# SCH_CLAP-SWITCH_2025-06-27.net
KiCad netlist of a schematic drawn in EasyEDA
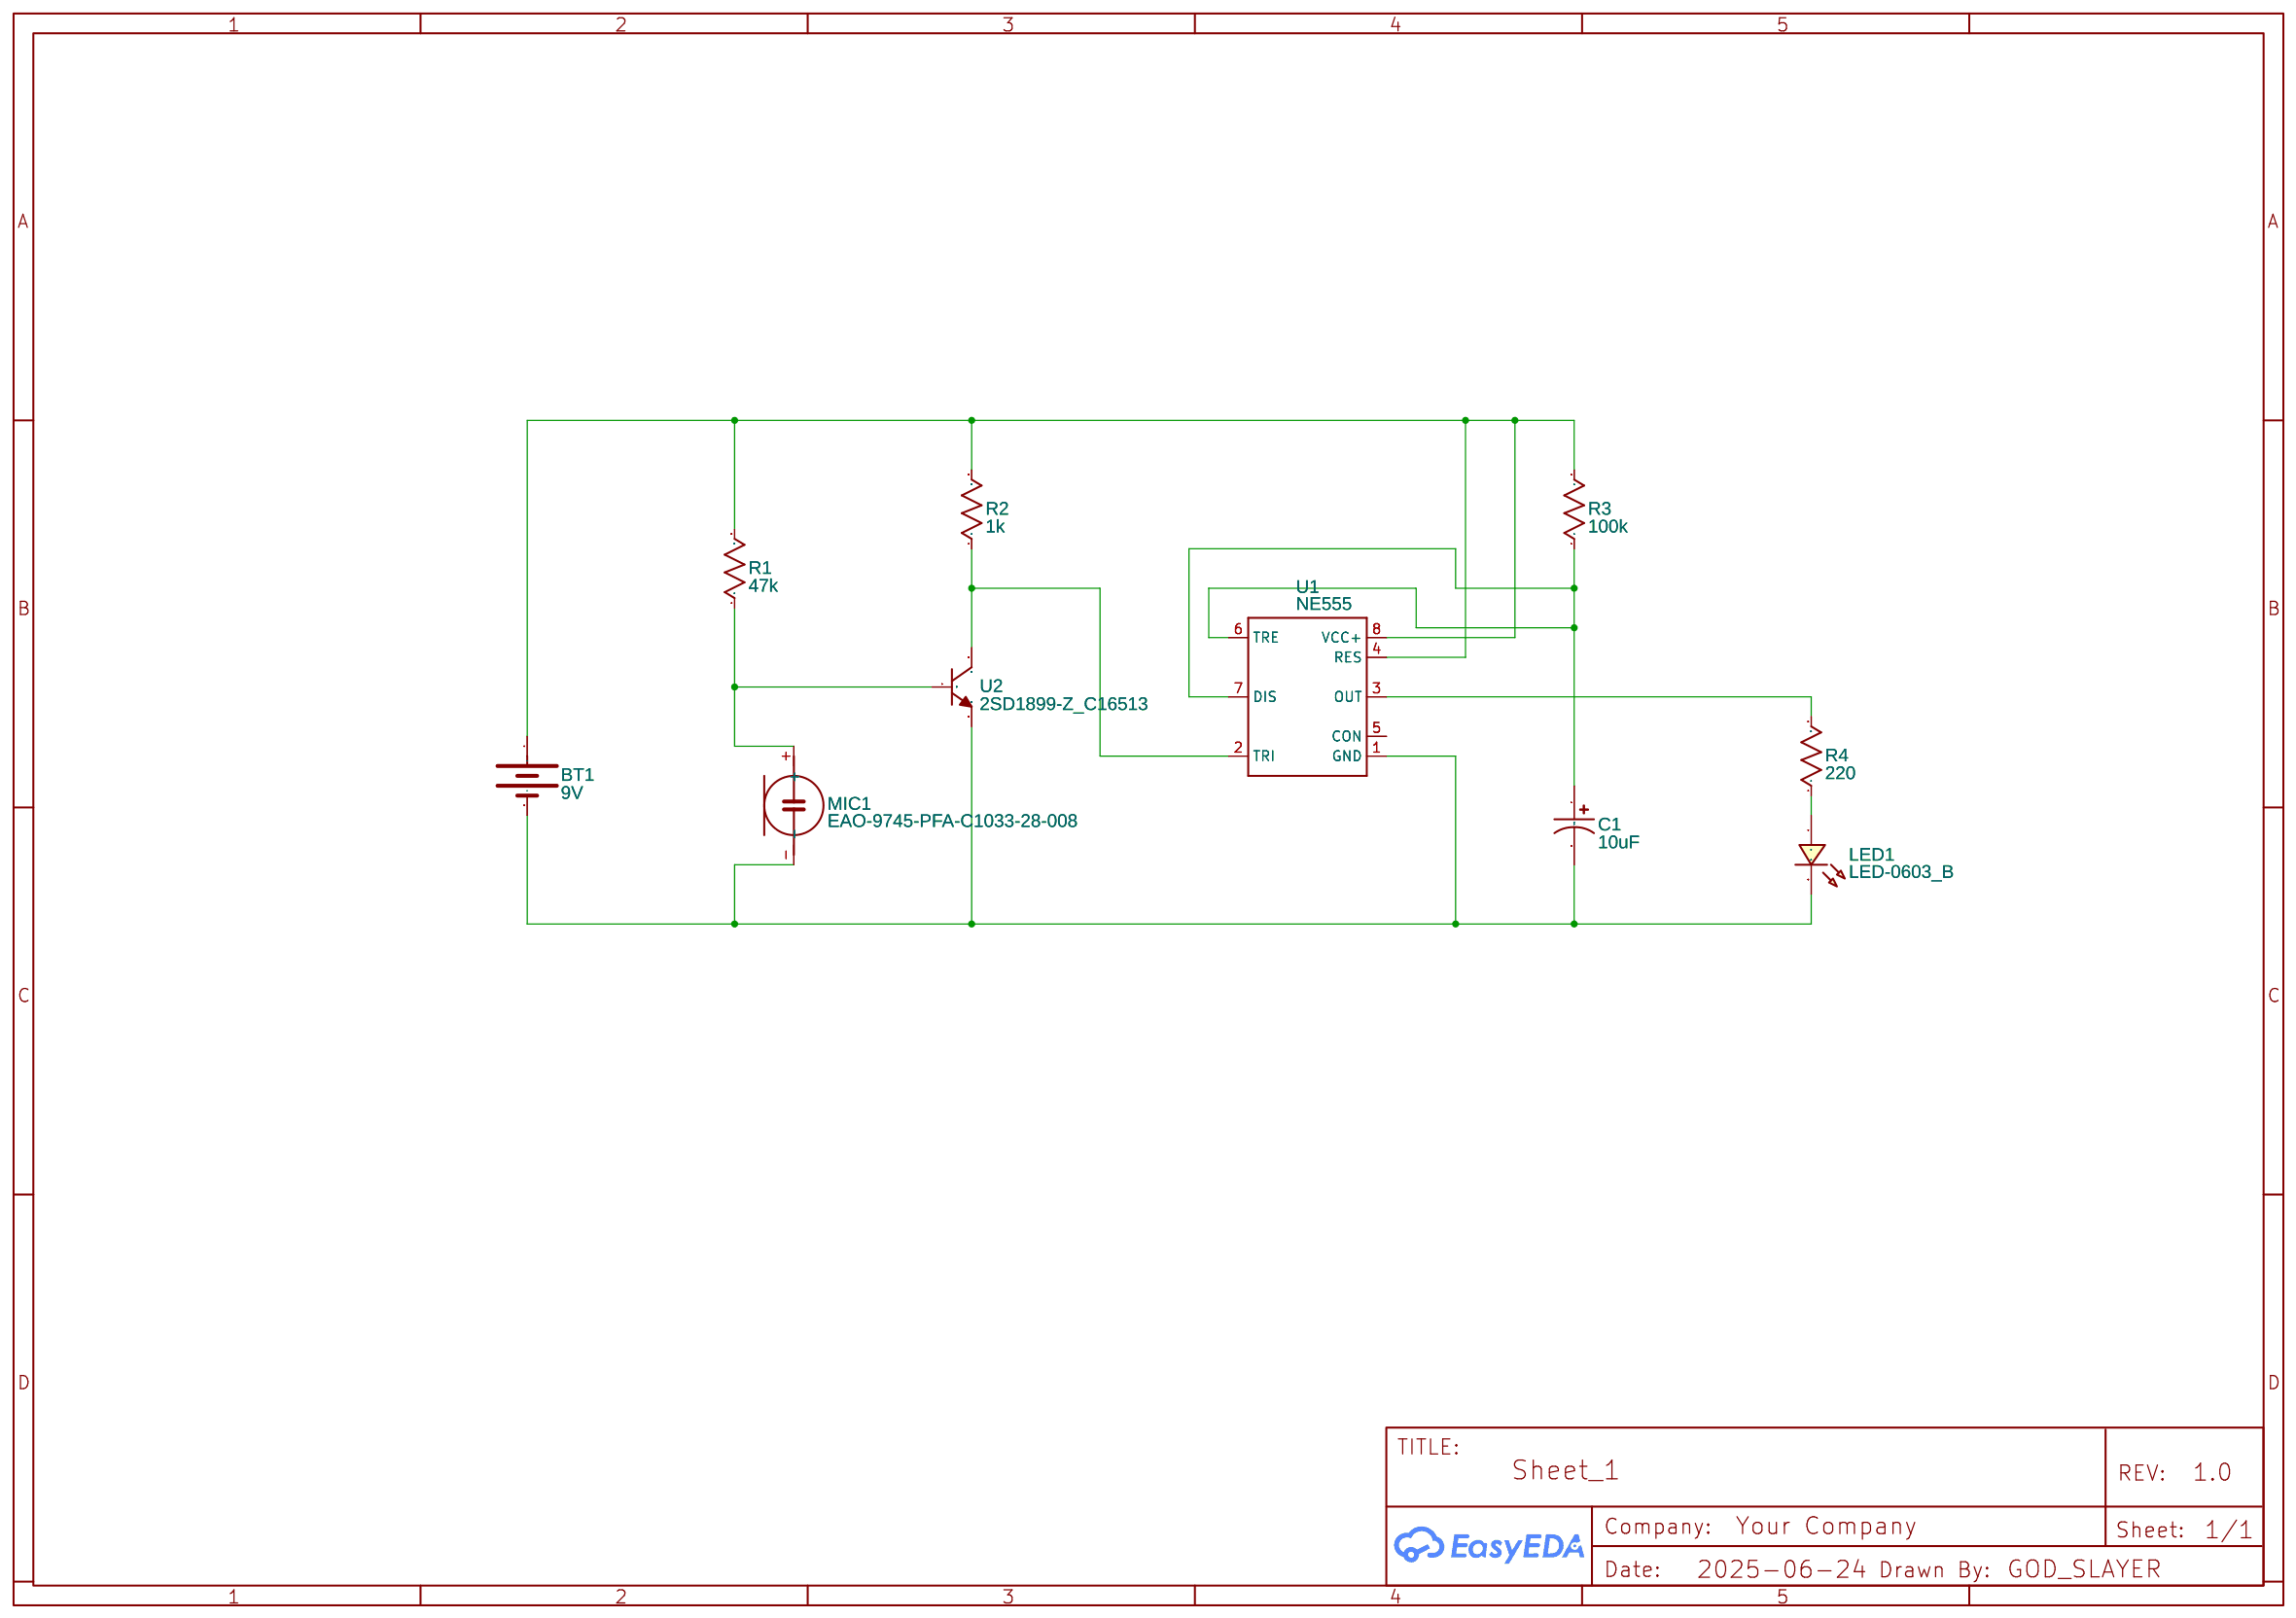
[diagram p0: schematic sheet]

(export (version "E")
  (design (tool "Eeschema 10.0.6"))
  (components
    (comp (ref "BT1")
      (value "9V")
      (fields (field (name "Manufacturer Part") "9V电池铜线扣 铜100mm") (field (name "Manufacturer") "Q&J"))
      (libsource (lib "") (part "9V电池铜线扣 铜100MM"))
    )
    (comp (ref "C1") (value "10uF") (libsource (lib "") (part "CE_SMD_D4.0×H5.5_US")))
    (comp (ref "LED1")
      (value "LED-0603_B")
      (fields
        (field (name "Manufacturer Part") "19-217/BHC-ZL1M2RY/3T")
        (field (name "Manufacturer") "EVERLIGHT(台湾亿光)")
      )
      (libsource (lib "") (part "LED-0603_B"))
    )
    (comp (ref "MIC1")
      (value "EAO-9745-PFA-C1033-28-008")
      (libsource (lib "") (part "EAO-9745-PFA-C1033-28-008"))
    )
    (comp (ref "R1") (value "47k") (libsource (lib "") (part "R_AXIAL-0.3_US")))
    (comp (ref "R2") (value "1k") (libsource (lib "") (part "R_AXIAL-0.3_US")))
    (comp (ref "R3") (value "100k") (libsource (lib "") (part "R_AXIAL-0.3_US")))
    (comp (ref "R4") (value "220") (libsource (lib "") (part "R_AXIAL-0.3_US")))
    (comp (ref "U1") (value "NE555") (libsource (lib "") (part "NE555")))
    (comp (ref "U2")
      (value "2SD1899-Z_C16513")
      (fields (field (name "Manufacturer Part") "2SD1899-Z") (field (name "Manufacturer") "CJ"))
      (libsource (lib "") (part "2SD1899-Z_C16513"))
    )
  )
  (nets
    (net (code "1") (name "Net-(BT1-+)") (class "Default")
      (node (ref "BT1") (pin "1") (pinfunction "+_1") (pintype "passive"))
      (node (ref "R1") (pin "2") (pinfunction "2_2") (pintype "unspecified"))
      (node (ref "R2") (pin "2") (pinfunction "2_2") (pintype "unspecified"))
      (node (ref "R3") (pin "2") (pinfunction "2_2") (pintype "unspecified"))
      (node (ref "U1") (pin "4") (pinfunction "RES_4") (pintype "input"))
      (node (ref "U1") (pin "8") (pinfunction "VCC+_8") (pintype "passive"))
    )
    (net (code "2") (name "Net-(BT1--)") (class "Default")
      (node (ref "BT1") (pin "2") (pinfunction "-_2") (pintype "passive"))
      (node (ref "C1") (pin "2") (pinfunction "2_2") (pintype "unspecified"))
      (node (ref "LED1") (pin "2") (pinfunction "2_2") (pintype "unspecified"))
      (node (ref "MIC1") (pin "-") (pinfunction "-_-") (pintype "unspecified"))
      (node (ref "U1") (pin "1") (pinfunction "GND_1") (pintype "passive"))
      (node (ref "U2") (pin "3") (pinfunction "E_3") (pintype "unspecified"))
    )
    (net (code "3") (name "Net-(LED1-Pad1)") (class "Default")
      (node (ref "LED1") (pin "1") (pinfunction "1_1") (pintype "unspecified"))
      (node (ref "R4") (pin "1") (pinfunction "1_1") (pintype "unspecified"))
    )
    (net (code "4") (name "Net-(U1-DIS)") (class "Default")
      (node (ref "C1") (pin "1") (pinfunction "1_1") (pintype "unspecified"))
      (node (ref "R3") (pin "1") (pinfunction "1_1") (pintype "unspecified"))
      (node (ref "U1") (pin "6") (pinfunction "TRE_6") (pintype "input"))
      (node (ref "U1") (pin "7") (pinfunction "DIS_7") (pintype "input"))
    )
    (net (code "5") (name "Net-(U1-OUT)") (class "Default")
      (node (ref "R4") (pin "2") (pinfunction "2_2") (pintype "unspecified"))
      (node (ref "U1") (pin "3") (pinfunction "OUT_3") (pintype "output"))
    )
    (net (code "6") (name "Net-(U1-TRI)") (class "Default")
      (node (ref "R2") (pin "1") (pinfunction "1_1") (pintype "unspecified"))
      (node (ref "U1") (pin "2") (pinfunction "TRI_2") (pintype "input"))
      (node (ref "U2") (pin "2") (pinfunction "C_2") (pintype "unspecified"))
    )
    (net (code "7") (name "Net-(U2-B)") (class "Default")
      (node (ref "MIC1") (pin "+") (pinfunction "+_+") (pintype "unspecified"))
      (node (ref "R1") (pin "1") (pinfunction "1_1") (pintype "unspecified"))
      (node (ref "U2") (pin "1") (pinfunction "B_1") (pintype "unspecified"))
    )
    (net (code "8") (name "unconnected-(U1-CON-Pad5)") (class "Default")
      (node (ref "U1") (pin "5") (pinfunction "CON_5") (pintype "input"))
    )
  )
)
